# Isolation.net
KiCad netlist of a schematic drawn in Altium Designer
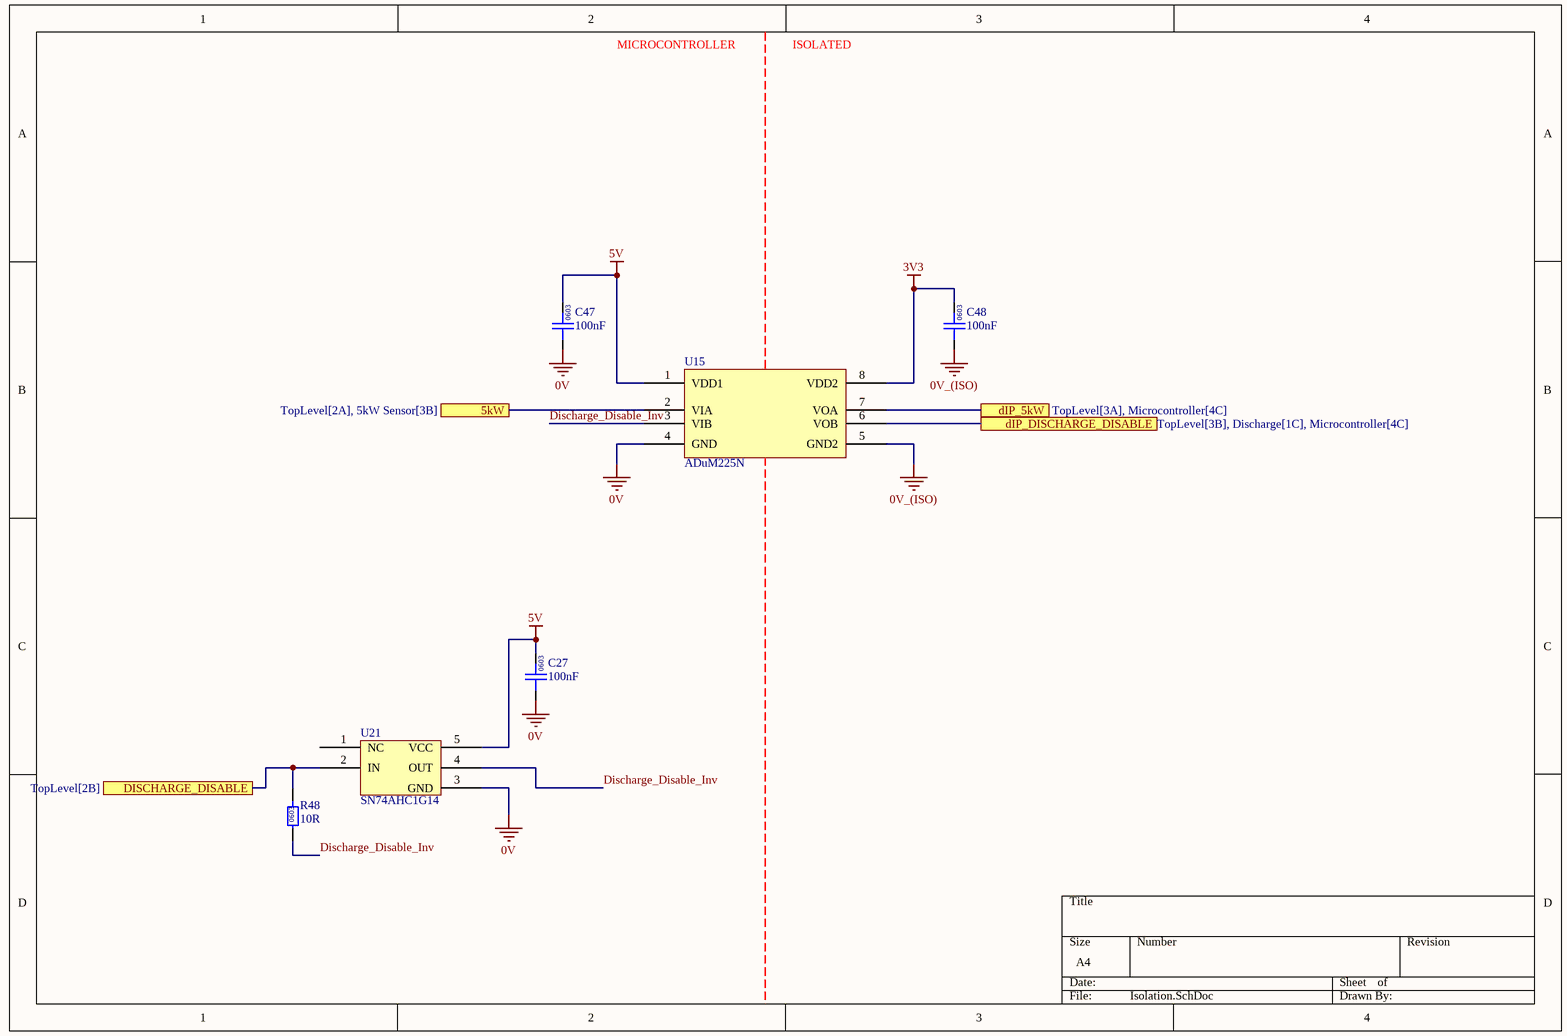
[diagram p0: Isolation.SchDoc]

(export (version "E")
  (design (tool "Eeschema 10.0.6"))
  (components
    (comp (ref "C27")
      (value "100nF")
      (footprint "0603")
      (fields
        (field (name "PART NUMBER") "GCM188L81H104KA57D")
        (field (name "MANUFACTURER") "muRata")
        (field (name "TOLERANCE") "±10%")
      )
      (libsource (lib "ts_standard_library") (part "Capacitor 0603"))
    )
    (comp (ref "C47")
      (value "100nF")
      (footprint "0603")
      (fields
        (field (name "PART NUMBER") "GCM188L81H104KA57D")
        (field (name "MANUFACTURER") "muRata")
        (field (name "TOLERANCE") "±10%")
      )
      (libsource (lib "ts_standard_library") (part "Capacitor 0603"))
    )
    (comp (ref "C48")
      (value "100nF")
      (footprint "0603")
      (fields
        (field (name "PART NUMBER") "GCM188L81H104KA57D")
        (field (name "MANUFACTURER") "muRata")
        (field (name "TOLERANCE") "±10%")
      )
      (libsource (lib "ts_standard_library") (part "Capacitor 0603"))
    )
    (comp (ref "R48")
      (value "10R")
      (footprint "0603")
      (fields
        (field (name "PART NUMBER") "RC0603FR-0710RL")
        (field (name "MANUFACTURER") "YAGEO")
        (field (name "TOLERANCE") "0.01")
      )
      (libsource (lib "ts_standard_library") (part "Resistor 0603"))
    )
    (comp (ref "U15")
      (value "ADuM225N")
      (footprint "AD-SOIC-8W")
      (description "DIGITAL ISOLATOR, DUAL CHANNEL")
      (fields (field (name "MANUFACTURER") "Analogue Devices"))
      (libsource (lib "ts_standard_library") (part "ADuM225N"))
    )
    (comp (ref "U21")
      (value "SN74AHC1G14")
      (footprint "SOT23-5_TI")
      (description "IC INVERTER 1CH 1-INP SOT23-5")
      (fields (field (name "MANUFACTURER") "Texas Instruments"))
      (libsource (lib "ts_standard_library") (part "SN74AHC1G14"))
    )
  )
  (nets
    (net (code "1") (name "/5kW") (class "Default")
      (node (ref "U15") (pin "2") (pinfunction "VIA_2") (pintype "passive"))
    )
    (net (code "2") (name "/DISCHARGE_DISABLE") (class "Default")
      (node (ref "R48") (pin "2") (pinfunction "2_2") (pintype "passive"))
      (node (ref "U21") (pin "2") (pinfunction "IN_2") (pintype "passive"))
    )
    (net (code "3") (name "/Discharge_Disable_Inv") (class "Default")
      (node (ref "R48") (pin "1") (pinfunction "1_1") (pintype "passive"))
      (node (ref "U15") (pin "3") (pinfunction "VIB_3") (pintype "passive"))
      (node (ref "U21") (pin "4") (pinfunction "OUT_4") (pintype "passive"))
    )
    (net (code "4") (name "/dIP_5kW") (class "Default")
      (node (ref "U15") (pin "7") (pinfunction "VOA_7") (pintype "passive"))
    )
    (net (code "5") (name "/dIP_DISCHARGE_DISABLE") (class "Default")
      (node (ref "U15") (pin "6") (pinfunction "VOB_6") (pintype "passive"))
    )
    (net (code "6") (name "0V") (class "Default")
      (node (ref "C27") (pin "1") (pinfunction "1_1") (pintype "passive"))
      (node (ref "C47") (pin "1") (pinfunction "1_1") (pintype "passive"))
      (node (ref "U15") (pin "4") (pinfunction "GND_4") (pintype "passive"))
      (node (ref "U21") (pin "3") (pinfunction "GND_3") (pintype "passive"))
    )
    (net (code "7") (name "0V_(ISO)") (class "Default")
      (node (ref "C48") (pin "1") (pinfunction "1_1") (pintype "passive"))
      (node (ref "U15") (pin "5") (pinfunction "GND2_5") (pintype "passive"))
    )
    (net (code "8") (name "3V3") (class "Default")
      (node (ref "C48") (pin "2") (pinfunction "2_2") (pintype "passive"))
      (node (ref "U15") (pin "8") (pinfunction "VDD2_8") (pintype "passive"))
    )
    (net (code "9") (name "5V") (class "Default")
      (node (ref "C27") (pin "2") (pinfunction "2_2") (pintype "passive"))
      (node (ref "C47") (pin "2") (pinfunction "2_2") (pintype "passive"))
      (node (ref "U15") (pin "1") (pinfunction "VDD1_1") (pintype "passive"))
      (node (ref "U21") (pin "5") (pinfunction "VCC_5") (pintype "passive"))
    )
    (net (code "10") (name "unconnected-(U21-NC-Pad1)") (class "Default")
      (node (ref "U21") (pin "1") (pinfunction "NC_1") (pintype "passive"))
    )
  )
)
